# quadstep.net
KiCad netlist of a schematic drawn in EAGLE
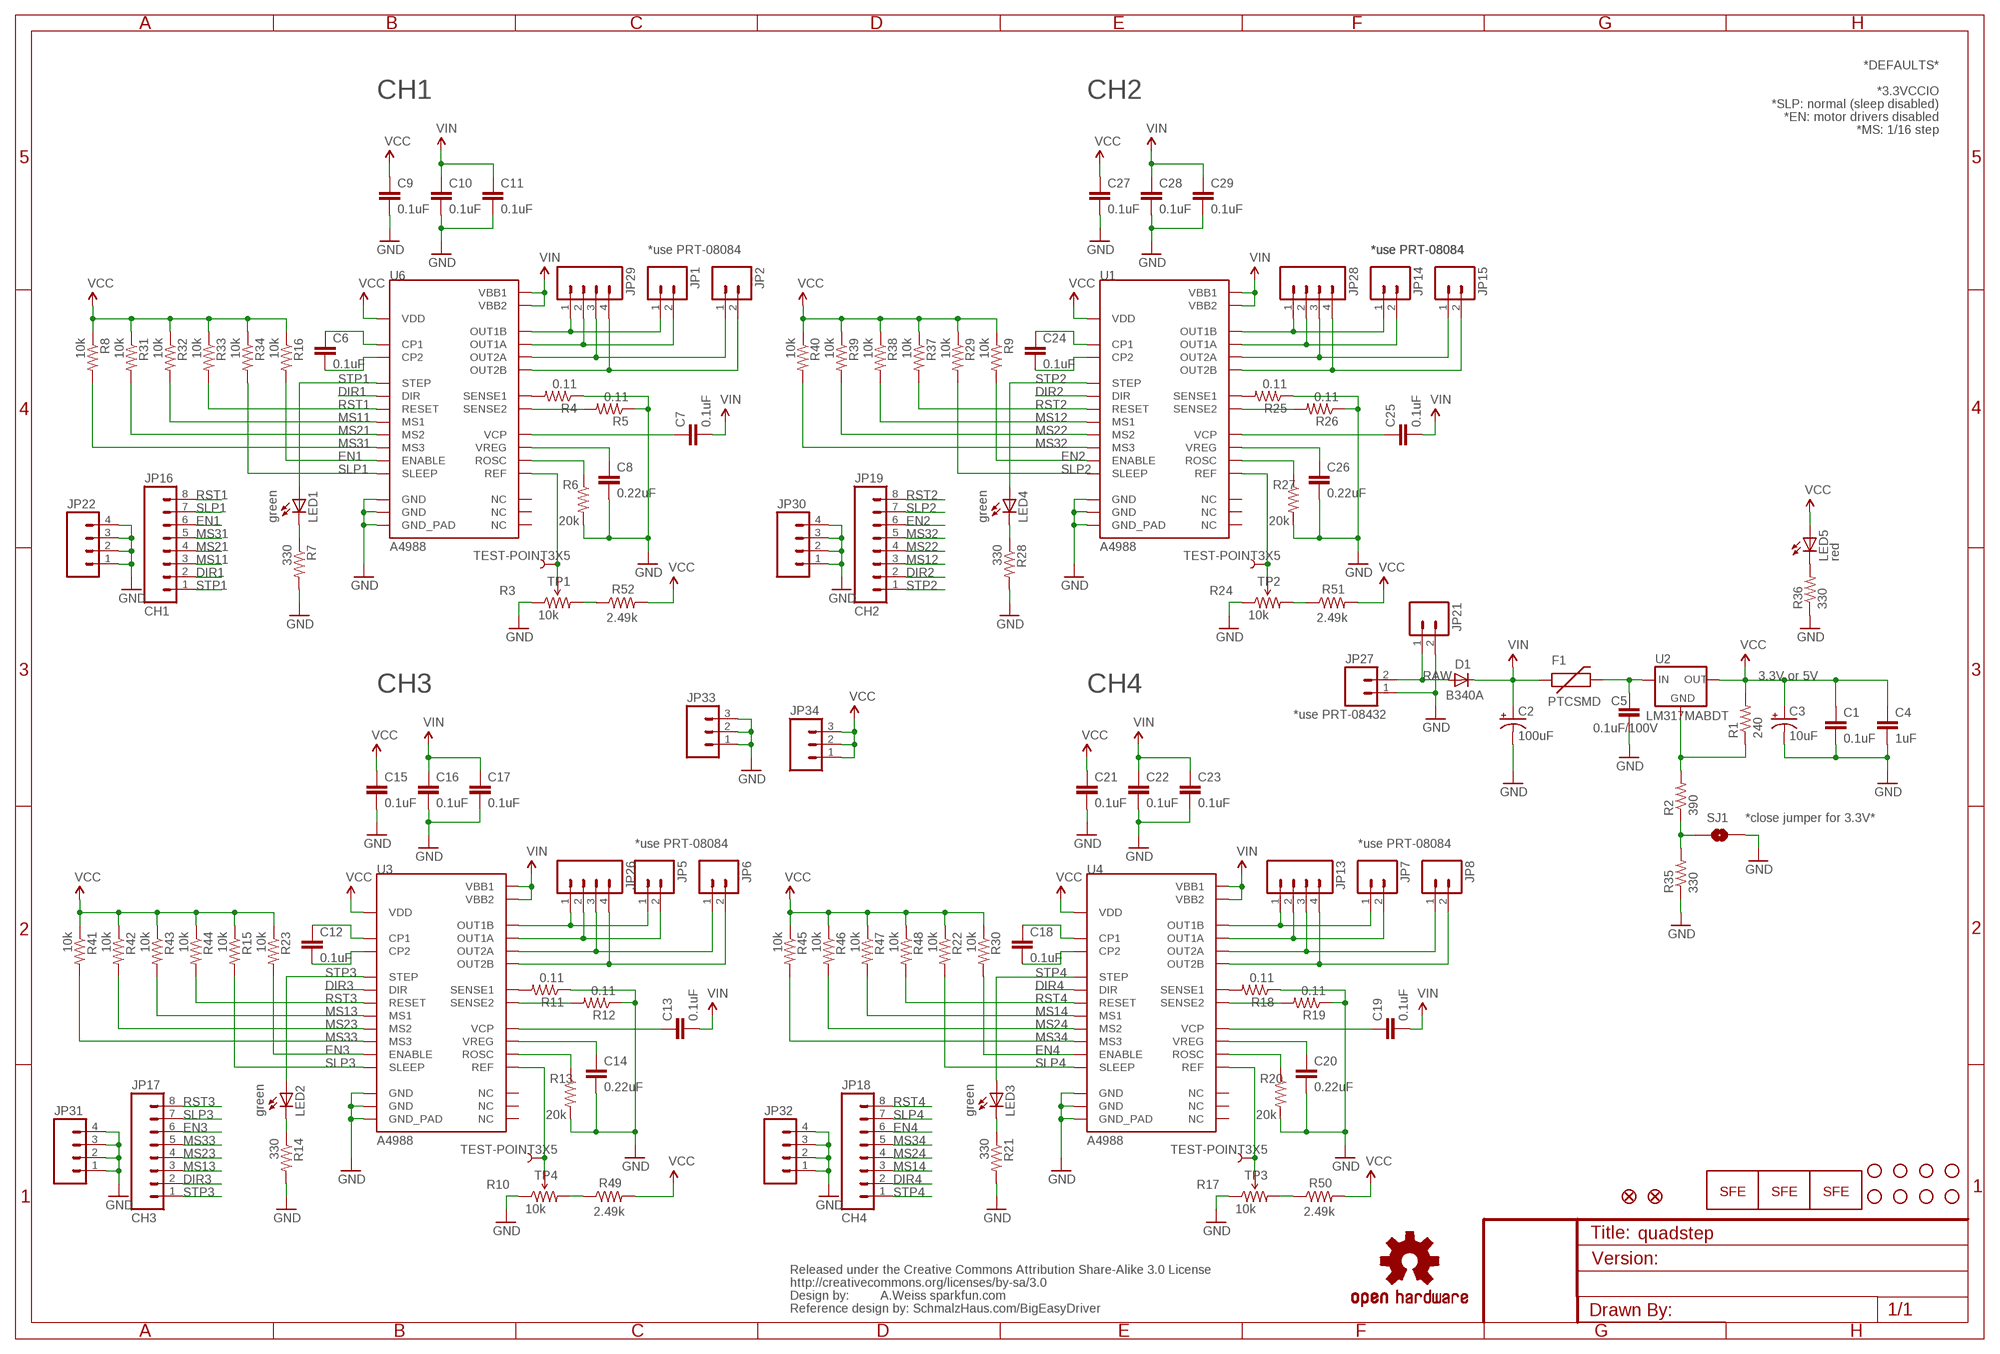
[diagram p0: schematic, sheet 1]

(export (version "E")
  (design (tool "Eeschema 10.0.6"))
  (components
    (comp (ref "C1")
      (value "0.1uF")
      (footprint "eagle-import:0402-CAP")
      (libsource (lib "eagle-import") (part "CAP0402-CAP"))
    )
    (comp (ref "C2")
      (value "100uF")
      (footprint "eagle-import:PANASONIC_G")
      (libsource (lib "eagle-import") (part "CAP_POLG"))
    )
    (comp (ref "C3")
      (value "10uF")
      (footprint "eagle-import:EIA3216")
      (libsource (lib "eagle-import") (part "CAP_POL1206"))
    )
    (comp (ref "C4")
      (value "1uF")
      (footprint "eagle-import:0805")
      (libsource (lib "eagle-import") (part "CAP0805"))
    )
    (comp (ref "C5")
      (value "0.1uF/100V")
      (footprint "eagle-import:0402-CAP")
      (libsource (lib "eagle-import") (part "CAP0402-CAP"))
    )
    (comp (ref "C6")
      (value "0.1uF")
      (footprint "eagle-import:0402-CAP")
      (libsource (lib "eagle-import") (part "CAP0402-CAP"))
    )
    (comp (ref "C7")
      (value "0.1uF")
      (footprint "eagle-import:0402-CAP")
      (libsource (lib "eagle-import") (part "CAP0402-CAP"))
    )
    (comp (ref "C8")
      (value "0.22uF")
      (footprint "eagle-import:0402-CAP")
      (libsource (lib "eagle-import") (part "CAP0402-CAP"))
    )
    (comp (ref "C9")
      (value "0.1uF")
      (footprint "eagle-import:0402-CAP")
      (libsource (lib "eagle-import") (part "CAP0402-CAP"))
    )
    (comp (ref "C10")
      (value "0.1uF")
      (footprint "eagle-import:0402-CAP")
      (libsource (lib "eagle-import") (part "CAP0402-CAP"))
    )
    (comp (ref "C11")
      (value "0.1uF")
      (footprint "eagle-import:0402-CAP")
      (libsource (lib "eagle-import") (part "CAP0402-CAP"))
    )
    (comp (ref "C12")
      (value "0.1uF")
      (footprint "eagle-import:0402-CAP")
      (libsource (lib "eagle-import") (part "CAP0402-CAP"))
    )
    (comp (ref "C13")
      (value "0.1uF")
      (footprint "eagle-import:0402-CAP")
      (libsource (lib "eagle-import") (part "CAP0402-CAP"))
    )
    (comp (ref "C14")
      (value "0.22uF")
      (footprint "eagle-import:0402-CAP")
      (libsource (lib "eagle-import") (part "CAP0402-CAP"))
    )
    (comp (ref "C15")
      (value "0.1uF")
      (footprint "eagle-import:0402-CAP")
      (libsource (lib "eagle-import") (part "CAP0402-CAP"))
    )
    (comp (ref "C16")
      (value "0.1uF")
      (footprint "eagle-import:0402-CAP")
      (libsource (lib "eagle-import") (part "CAP0402-CAP"))
    )
    (comp (ref "C17")
      (value "0.1uF")
      (footprint "eagle-import:0402-CAP")
      (libsource (lib "eagle-import") (part "CAP0402-CAP"))
    )
    (comp (ref "C18")
      (value "0.1uF")
      (footprint "eagle-import:0402-CAP")
      (libsource (lib "eagle-import") (part "CAP0402-CAP"))
    )
    (comp (ref "C19")
      (value "0.1uF")
      (footprint "eagle-import:0402-CAP")
      (libsource (lib "eagle-import") (part "CAP0402-CAP"))
    )
    (comp (ref "C20")
      (value "0.22uF")
      (footprint "eagle-import:0402-CAP")
      (libsource (lib "eagle-import") (part "CAP0402-CAP"))
    )
    (comp (ref "C21")
      (value "0.1uF")
      (footprint "eagle-import:0402-CAP")
      (libsource (lib "eagle-import") (part "CAP0402-CAP"))
    )
    (comp (ref "C22")
      (value "0.1uF")
      (footprint "eagle-import:0402-CAP")
      (libsource (lib "eagle-import") (part "CAP0402-CAP"))
    )
    (comp (ref "C23")
      (value "0.1uF")
      (footprint "eagle-import:0402-CAP")
      (libsource (lib "eagle-import") (part "CAP0402-CAP"))
    )
    (comp (ref "C24")
      (value "0.1uF")
      (footprint "eagle-import:0402-CAP")
      (libsource (lib "eagle-import") (part "CAP0402-CAP"))
    )
    (comp (ref "C25")
      (value "0.1uF")
      (footprint "eagle-import:0402-CAP")
      (libsource (lib "eagle-import") (part "CAP0402-CAP"))
    )
    (comp (ref "C26")
      (value "0.22uF")
      (footprint "eagle-import:0402-CAP")
      (libsource (lib "eagle-import") (part "CAP0402-CAP"))
    )
    (comp (ref "C27")
      (value "0.1uF")
      (footprint "eagle-import:0402-CAP")
      (libsource (lib "eagle-import") (part "CAP0402-CAP"))
    )
    (comp (ref "C28")
      (value "0.1uF")
      (footprint "eagle-import:0402-CAP")
      (libsource (lib "eagle-import") (part "CAP0402-CAP"))
    )
    (comp (ref "C29")
      (value "0.1uF")
      (footprint "eagle-import:0402-CAP")
      (libsource (lib "eagle-import") (part "CAP0402-CAP"))
    )
    (comp (ref "CC_TEXT1")
      (value "CREATIVE_COMMONS")
      (footprint "eagle-import:CREATIVE_COMMONS")
      (libsource (lib "eagle-import") (part "CREATIVE_COMMONS"))
    )
    (comp (ref "D1")
      (value "B340A")
      (footprint "eagle-import:SMA-DIODE")
      (libsource (lib "eagle-import") (part "DIODESMA"))
    )
    (comp (ref "F1")
      (value "PTCSMD")
      (footprint "eagle-import:PTC-1206")
      (libsource (lib "eagle-import") (part "PTCSMD"))
    )
    (comp (ref "JP1")
      (value "M023.5MM_LOCK")
      (footprint "eagle-import:SCREWTERMINAL-3.5MM-2_LOCK")
      (libsource (lib "eagle-import") (part "M023.5MM_LOCK"))
    )
    (comp (ref "JP2")
      (value "M023.5MM_LOCK")
      (footprint "eagle-import:SCREWTERMINAL-3.5MM-2_LOCK")
      (libsource (lib "eagle-import") (part "M023.5MM_LOCK"))
    )
    (comp (ref "JP5")
      (value "M023.5MM_LOCK")
      (footprint "eagle-import:SCREWTERMINAL-3.5MM-2_LOCK")
      (libsource (lib "eagle-import") (part "M023.5MM_LOCK"))
    )
    (comp (ref "JP6")
      (value "M023.5MM_LOCK")
      (footprint "eagle-import:SCREWTERMINAL-3.5MM-2_LOCK")
      (libsource (lib "eagle-import") (part "M023.5MM_LOCK"))
    )
    (comp (ref "JP7")
      (value "M023.5MM_LOCK")
      (footprint "eagle-import:SCREWTERMINAL-3.5MM-2_LOCK")
      (libsource (lib "eagle-import") (part "M023.5MM_LOCK"))
    )
    (comp (ref "JP8")
      (value "M023.5MM_LOCK")
      (footprint "eagle-import:SCREWTERMINAL-3.5MM-2_LOCK")
      (libsource (lib "eagle-import") (part "M023.5MM_LOCK"))
    )
    (comp (ref "JP9")
      (value "STAND-OFF")
      (footprint "eagle-import:STAND-OFF")
      (libsource (lib "eagle-import") (part "STAND-OFF"))
    )
    (comp (ref "JP10")
      (value "STAND-OFF")
      (footprint "eagle-import:STAND-OFF")
      (libsource (lib "eagle-import") (part "STAND-OFF"))
    )
    (comp (ref "JP11")
      (value "STAND-OFF")
      (footprint "eagle-import:STAND-OFF")
      (libsource (lib "eagle-import") (part "STAND-OFF"))
    )
    (comp (ref "JP12")
      (value "STAND-OFF")
      (footprint "eagle-import:STAND-OFF")
      (libsource (lib "eagle-import") (part "STAND-OFF"))
    )
    (comp (ref "JP13")
      (value "M04PTH")
      (footprint "eagle-import:1X04")
      (libsource (lib "eagle-import") (part "M04PTH"))
    )
    (comp (ref "JP14")
      (value "M023.5MM_LOCK")
      (footprint "eagle-import:SCREWTERMINAL-3.5MM-2_LOCK")
      (libsource (lib "eagle-import") (part "M023.5MM_LOCK"))
    )
    (comp (ref "JP15")
      (value "M023.5MM_LOCK")
      (footprint "eagle-import:SCREWTERMINAL-3.5MM-2_LOCK")
      (libsource (lib "eagle-import") (part "M023.5MM_LOCK"))
    )
    (comp (ref "JP16")
      (value "CH1")
      (footprint "eagle-import:1X08")
      (libsource (lib "eagle-import") (part "M08"))
    )
    (comp (ref "JP17")
      (value "CH3")
      (footprint "eagle-import:1X08")
      (libsource (lib "eagle-import") (part "M08"))
    )
    (comp (ref "JP18")
      (value "CH4")
      (footprint "eagle-import:1X08")
      (libsource (lib "eagle-import") (part "M08"))
    )
    (comp (ref "JP19")
      (value "CH2")
      (footprint "eagle-import:1X08")
      (libsource (lib "eagle-import") (part "M08"))
    )
    (comp (ref "JP20")
      (value "LOGO-SFENEW")
      (footprint "eagle-import:SFE-NEW-WEBLOGO")
      (libsource (lib "eagle-import") (part "LOGO-SFENEW"))
    )
    (comp (ref "JP21")
      (value "M025MM")
      (footprint "eagle-import:SCREWTERMINAL-5MM-2")
      (libsource (lib "eagle-import") (part "M025MM"))
    )
    (comp (ref "JP22")
      (value "M04PTH")
      (footprint "eagle-import:1X04")
      (libsource (lib "eagle-import") (part "M04PTH"))
    )
    (comp (ref "JP23")
      (value "LOGO-SFESK")
      (footprint "eagle-import:SFE-LOGO-FLAME")
      (libsource (lib "eagle-import") (part "LOGO-SFESK"))
    )
    (comp (ref "JP24")
      (value "FIDUCIAL1X2")
      (footprint "eagle-import:FIDUCIAL-1X2")
      (libsource (lib "eagle-import") (part "FIDUCIAL1X2"))
    )
    (comp (ref "JP25")
      (value "FIDUCIAL1X2")
      (footprint "eagle-import:FIDUCIAL-1X2")
      (libsource (lib "eagle-import") (part "FIDUCIAL1X2"))
    )
    (comp (ref "JP26")
      (value "M04PTH")
      (footprint "eagle-import:1X04")
      (libsource (lib "eagle-import") (part "M04PTH"))
    )
    (comp (ref "JP27")
      (value "M02PTH")
      (footprint "eagle-import:1X02")
      (libsource (lib "eagle-import") (part "SparkFun-Connectors_M02PTH"))
    )
    (comp (ref "JP28")
      (value "M04PTH")
      (footprint "eagle-import:1X04")
      (libsource (lib "eagle-import") (part "M04PTH"))
    )
    (comp (ref "JP29")
      (value "M04PTH")
      (footprint "eagle-import:1X04")
      (libsource (lib "eagle-import") (part "M04PTH"))
    )
    (comp (ref "JP30")
      (value "M04PTH")
      (footprint "eagle-import:1X04")
      (libsource (lib "eagle-import") (part "M04PTH"))
    )
    (comp (ref "JP31")
      (value "M04PTH")
      (footprint "eagle-import:1X04")
      (libsource (lib "eagle-import") (part "M04PTH"))
    )
    (comp (ref "JP32")
      (value "M04PTH")
      (footprint "eagle-import:1X04")
      (libsource (lib "eagle-import") (part "M04PTH"))
    )
    (comp (ref "JP33")
      (value "M03PTH")
      (footprint "eagle-import:1X03")
      (libsource (lib "eagle-import") (part "M03PTH"))
    )
    (comp (ref "JP34")
      (value "M03PTH")
      (footprint "eagle-import:1X03")
      (libsource (lib "eagle-import") (part "M03PTH"))
    )
    (comp (ref "LED1")
      (value "green")
      (footprint "eagle-import:LED-0603")
      (libsource (lib "eagle-import") (part "LED0603"))
    )
    (comp (ref "LED2")
      (value "green")
      (footprint "eagle-import:LED-0603")
      (libsource (lib "eagle-import") (part "LED0603"))
    )
    (comp (ref "LED3")
      (value "green")
      (footprint "eagle-import:LED-0603")
      (libsource (lib "eagle-import") (part "LED0603"))
    )
    (comp (ref "LED4")
      (value "green")
      (footprint "eagle-import:LED-0603")
      (libsource (lib "eagle-import") (part "LED0603"))
    )
    (comp (ref "LED5")
      (value "red")
      (footprint "eagle-import:LED-0603")
      (libsource (lib "eagle-import") (part "LED0603"))
    )
    (comp (ref "LOGO1")
      (value "LOGO-SFENW2")
      (footprint "eagle-import:SFE-NEW-WEB")
      (libsource (lib "eagle-import") (part "SparkFun-Aesthetics_LOGO-SFENW2"))
    )
    (comp (ref "R1")
      (value "240")
      (footprint "eagle-import:0402-RES")
      (libsource (lib "eagle-import") (part "RESISTOR0402-RES"))
    )
    (comp (ref "R2")
      (value "390")
      (footprint "eagle-import:0402-RES")
      (libsource (lib "eagle-import") (part "RESISTOR0402-RES"))
    )
    (comp (ref "R3")
      (value "10k")
      (footprint "eagle-import:TRIMPOT-3MM")
      (libsource (lib "eagle-import") (part "TRIMPOTSMD"))
    )
    (comp (ref "R4")
      (value "0.11")
      (footprint "eagle-import:R2010")
      (libsource (lib "eagle-import") (part "RESISTOR2010"))
    )
    (comp (ref "R5")
      (value "0.11")
      (footprint "eagle-import:R2010")
      (libsource (lib "eagle-import") (part "RESISTOR2010"))
    )
    (comp (ref "R6")
      (value "20k")
      (footprint "eagle-import:0402-RES")
      (libsource (lib "eagle-import") (part "RESISTOR0402-RES"))
    )
    (comp (ref "R7")
      (value "330")
      (footprint "eagle-import:0402-RES")
      (libsource (lib "eagle-import") (part "RESISTOR0402-RES"))
    )
    (comp (ref "R8")
      (value "10k")
      (footprint "eagle-import:0402-RES")
      (libsource (lib "eagle-import") (part "RESISTOR0402-RES"))
    )
    (comp (ref "R9")
      (value "10k")
      (footprint "eagle-import:0402-RES")
      (libsource (lib "eagle-import") (part "RESISTOR0402-RES"))
    )
    (comp (ref "R10")
      (value "10k")
      (footprint "eagle-import:TRIMPOT-3MM")
      (libsource (lib "eagle-import") (part "TRIMPOTSMD"))
    )
    (comp (ref "R11")
      (value "0.11")
      (footprint "eagle-import:R2010")
      (libsource (lib "eagle-import") (part "RESISTOR2010"))
    )
    (comp (ref "R12")
      (value "0.11")
      (footprint "eagle-import:R2010")
      (libsource (lib "eagle-import") (part "RESISTOR2010"))
    )
    (comp (ref "R13")
      (value "20k")
      (footprint "eagle-import:0402-RES")
      (libsource (lib "eagle-import") (part "RESISTOR0402-RES"))
    )
    (comp (ref "R14")
      (value "330")
      (footprint "eagle-import:0402-RES")
      (libsource (lib "eagle-import") (part "RESISTOR0402-RES"))
    )
    (comp (ref "R15")
      (value "10k")
      (footprint "eagle-import:0402-RES")
      (libsource (lib "eagle-import") (part "RESISTOR0402-RES"))
    )
    (comp (ref "R16")
      (value "10k")
      (footprint "eagle-import:0402-RES")
      (libsource (lib "eagle-import") (part "RESISTOR0402-RES"))
    )
    (comp (ref "R17")
      (value "10k")
      (footprint "eagle-import:TRIMPOT-3MM")
      (libsource (lib "eagle-import") (part "TRIMPOTSMD"))
    )
    (comp (ref "R18")
      (value "0.11")
      (footprint "eagle-import:R2010")
      (libsource (lib "eagle-import") (part "RESISTOR2010"))
    )
    (comp (ref "R19")
      (value "0.11")
      (footprint "eagle-import:R2010")
      (libsource (lib "eagle-import") (part "RESISTOR2010"))
    )
    (comp (ref "R20")
      (value "20k")
      (footprint "eagle-import:0402-RES")
      (libsource (lib "eagle-import") (part "RESISTOR0402-RES"))
    )
    (comp (ref "R21")
      (value "330")
      (footprint "eagle-import:0402-RES")
      (libsource (lib "eagle-import") (part "RESISTOR0402-RES"))
    )
    (comp (ref "R22")
      (value "10k")
      (footprint "eagle-import:0402-RES")
      (libsource (lib "eagle-import") (part "RESISTOR0402-RES"))
    )
    (comp (ref "R23")
      (value "10k")
      (footprint "eagle-import:0402-RES")
      (libsource (lib "eagle-import") (part "RESISTOR0402-RES"))
    )
    (comp (ref "R24")
      (value "10k")
      (footprint "eagle-import:TRIMPOT-3MM")
      (libsource (lib "eagle-import") (part "TRIMPOTSMD"))
    )
    (comp (ref "R25")
      (value "0.11")
      (footprint "eagle-import:R2010")
      (libsource (lib "eagle-import") (part "RESISTOR2010"))
    )
    (comp (ref "R26")
      (value "0.11")
      (footprint "eagle-import:R2010")
      (libsource (lib "eagle-import") (part "RESISTOR2010"))
    )
    (comp (ref "R27")
      (value "20k")
      (footprint "eagle-import:0402-RES")
      (libsource (lib "eagle-import") (part "RESISTOR0402-RES"))
    )
    (comp (ref "R28")
      (value "330")
      (footprint "eagle-import:0402-RES")
      (libsource (lib "eagle-import") (part "RESISTOR0402-RES"))
    )
    (comp (ref "R29")
      (value "10k")
      (footprint "eagle-import:0402-RES")
      (libsource (lib "eagle-import") (part "RESISTOR0402-RES"))
    )
    (comp (ref "R30")
      (value "10k")
      (footprint "eagle-import:0402-RES")
      (libsource (lib "eagle-import") (part "RESISTOR0402-RES"))
    )
    (comp (ref "R31")
      (value "10k")
      (footprint "eagle-import:0402-RES")
      (libsource (lib "eagle-import") (part "RESISTOR0402-RES"))
    )
    (comp (ref "R32")
      (value "10k")
      (footprint "eagle-import:0402-RES")
      (libsource (lib "eagle-import") (part "RESISTOR0402-RES"))
    )
    (comp (ref "R33")
      (value "10k")
      (footprint "eagle-import:0402-RES")
      (libsource (lib "eagle-import") (part "RESISTOR0402-RES"))
    )
    (comp (ref "R34")
      (value "10k")
      (footprint "eagle-import:0402-RES")
      (libsource (lib "eagle-import") (part "RESISTOR0402-RES"))
    )
    (comp (ref "R35")
      (value "330")
      (footprint "eagle-import:0402-RES")
      (libsource (lib "eagle-import") (part "RESISTOR0402-RES"))
    )
    (comp (ref "R36")
      (value "330")
      (footprint "eagle-import:0402-RES")
      (libsource (lib "eagle-import") (part "RESISTOR0402-RES"))
    )
    (comp (ref "R37")
      (value "10k")
      (footprint "eagle-import:0402-RES")
      (libsource (lib "eagle-import") (part "RESISTOR0402-RES"))
    )
    (comp (ref "R38")
      (value "10k")
      (footprint "eagle-import:0402-RES")
      (libsource (lib "eagle-import") (part "RESISTOR0402-RES"))
    )
    (comp (ref "R39")
      (value "10k")
      (footprint "eagle-import:0402-RES")
      (libsource (lib "eagle-import") (part "RESISTOR0402-RES"))
    )
    (comp (ref "R40")
      (value "10k")
      (footprint "eagle-import:0402-RES")
      (libsource (lib "eagle-import") (part "RESISTOR0402-RES"))
    )
    (comp (ref "R41")
      (value "10k")
      (footprint "eagle-import:0402-RES")
      (libsource (lib "eagle-import") (part "RESISTOR0402-RES"))
    )
    (comp (ref "R42")
      (value "10k")
      (footprint "eagle-import:0402-RES")
      (libsource (lib "eagle-import") (part "RESISTOR0402-RES"))
    )
    (comp (ref "R43")
      (value "10k")
      (footprint "eagle-import:0402-RES")
      (libsource (lib "eagle-import") (part "RESISTOR0402-RES"))
    )
    (comp (ref "R44")
      (value "10k")
      (footprint "eagle-import:0402-RES")
      (libsource (lib "eagle-import") (part "RESISTOR0402-RES"))
    )
    (comp (ref "R45")
      (value "10k")
      (footprint "eagle-import:0402-RES")
      (libsource (lib "eagle-import") (part "RESISTOR0402-RES"))
    )
    (comp (ref "R46")
      (value "10k")
      (footprint "eagle-import:0402-RES")
      (libsource (lib "eagle-import") (part "RESISTOR0402-RES"))
    )
    (comp (ref "R47")
      (value "10k")
      (footprint "eagle-import:0402-RES")
      (libsource (lib "eagle-import") (part "RESISTOR0402-RES"))
    )
    (comp (ref "R48")
      (value "10k")
      (footprint "eagle-import:0402-RES")
      (libsource (lib "eagle-import") (part "RESISTOR0402-RES"))
    )
    (comp (ref "R49")
      (value "2.49k")
      (footprint "eagle-import:0402-RES")
      (libsource (lib "eagle-import") (part "RESISTOR0402-RES"))
    )
    (comp (ref "R50")
      (value "2.49k")
      (footprint "eagle-import:0402-RES")
      (libsource (lib "eagle-import") (part "RESISTOR0402-RES"))
    )
    (comp (ref "R51")
      (value "2.49k")
      (footprint "eagle-import:0402-RES")
      (libsource (lib "eagle-import") (part "RESISTOR0402-RES"))
    )
    (comp (ref "R52")
      (value "2.49k")
      (footprint "eagle-import:0402-RES")
      (libsource (lib "eagle-import") (part "RESISTOR0402-RES"))
    )
    (comp (ref "SJ1")
      (value "SOLDERJUMPERNO")
      (footprint "eagle-import:SJ_2S-NO")
      (libsource (lib "eagle-import") (part "SOLDERJUMPERNO"))
    )
    (comp (ref "STANDOFF1")
      (value "STAND-OFFTIGHT")
      (footprint "eagle-import:STAND-OFF-TIGHT")
      (libsource (lib "eagle-import") (part "SparkFun-Electromechanical_STAND-OFFTIGHT"))
    )
    (comp (ref "STANDOFF2")
      (value "STAND-OFFTIGHT")
      (footprint "eagle-import:STAND-OFF-TIGHT")
      (libsource (lib "eagle-import") (part "SparkFun-Electromechanical_STAND-OFFTIGHT"))
    )
    (comp (ref "STANDOFF3")
      (value "STAND-OFFTIGHT")
      (footprint "eagle-import:STAND-OFF-TIGHT")
      (libsource (lib "eagle-import") (part "SparkFun-Electromechanical_STAND-OFFTIGHT"))
    )
    (comp (ref "STANDOFF4")
      (value "STAND-OFFTIGHT")
      (footprint "eagle-import:STAND-OFF-TIGHT")
      (libsource (lib "eagle-import") (part "SparkFun-Electromechanical_STAND-OFFTIGHT"))
    )
    (comp (ref "TP1")
      (value "TEST-POINT3X5")
      (footprint "eagle-import:PAD.03X.05")
      (libsource (lib "eagle-import") (part "TEST-POINT3X5"))
    )
    (comp (ref "TP2")
      (value "TEST-POINT3X5")
      (footprint "eagle-import:PAD.03X.05")
      (libsource (lib "eagle-import") (part "TEST-POINT3X5"))
    )
    (comp (ref "TP3")
      (value "TEST-POINT3X5")
      (footprint "eagle-import:PAD.03X.05")
      (libsource (lib "eagle-import") (part "TEST-POINT3X5"))
    )
    (comp (ref "TP4")
      (value "TEST-POINT3X5")
      (footprint "eagle-import:PAD.03X.05")
      (libsource (lib "eagle-import") (part "TEST-POINT3X5"))
    )
    (comp (ref "U$1")
      (value "OSHW-LOGOS")
      (footprint "eagle-import:OSHW-LOGO-S")
      (libsource (lib "eagle-import") (part "OSHW-LOGOS"))
    )
    (comp (ref "U1")
      (value "A4988")
      (footprint "eagle-import:QFN-28-5MM-1_1")
      (libsource (lib "eagle-import") (part "A49831{colon}1"))
    )
    (comp (ref "U2")
      (value "LM317MABDT")
      (footprint "eagle-import:DPAK")
      (libsource (lib "eagle-import") (part "V_REG_MC33269DT"))
    )
    (comp (ref "U3")
      (value "A4988")
      (footprint "eagle-import:QFN-28-5MM-1_1")
      (libsource (lib "eagle-import") (part "A49831{colon}1"))
    )
    (comp (ref "U4")
      (value "A4988")
      (footprint "eagle-import:QFN-28-5MM-1_1")
      (libsource (lib "eagle-import") (part "A49831{colon}1"))
    )
    (comp (ref "U6")
      (value "A4988")
      (footprint "eagle-import:QFN-28-5MM-1_1")
      (libsource (lib "eagle-import") (part "A49831{colon}1"))
    )
  )
  (nets
    (net (code "1") (name "/DIR1") (class "Default")
      (node (ref "JP16") (pin "2") (pinfunction "2_2") (pintype "passive"))
      (node (ref "U6") (pin "P$19") (pinfunction "DIR_P$19") (pintype "input"))
    )
    (net (code "2") (name "/DIR2") (class "Default")
      (node (ref "JP19") (pin "2") (pinfunction "2_2") (pintype "passive"))
      (node (ref "U1") (pin "P$19") (pinfunction "DIR_P$19") (pintype "input"))
    )
    (net (code "3") (name "/DIR3") (class "Default")
      (node (ref "JP17") (pin "2") (pinfunction "2_2") (pintype "passive"))
      (node (ref "U3") (pin "P$19") (pinfunction "DIR_P$19") (pintype "input"))
    )
    (net (code "4") (name "/DIR4") (class "Default")
      (node (ref "JP18") (pin "2") (pinfunction "2_2") (pintype "passive"))
      (node (ref "U4") (pin "P$19") (pinfunction "DIR_P$19") (pintype "input"))
    )
    (net (code "5") (name "/EN1") (class "Default")
      (node (ref "JP16") (pin "6") (pinfunction "6_6") (pintype "passive"))
      (node (ref "R16") (pin "2") (pinfunction "2_2") (pintype "passive"))
      (node (ref "U6") (pin "P$2") (pinfunction "ENABLE_P$2") (pintype "input"))
    )
    (net (code "6") (name "/EN2") (class "Default")
      (node (ref "JP19") (pin "6") (pinfunction "6_6") (pintype "passive"))
      (node (ref "R9") (pin "2") (pinfunction "2_2") (pintype "passive"))
      (node (ref "U1") (pin "P$2") (pinfunction "ENABLE_P$2") (pintype "input"))
    )
    (net (code "7") (name "/EN3") (class "Default")
      (node (ref "JP17") (pin "6") (pinfunction "6_6") (pintype "passive"))
      (node (ref "R23") (pin "2") (pinfunction "2_2") (pintype "passive"))
      (node (ref "U3") (pin "P$2") (pinfunction "ENABLE_P$2") (pintype "input"))
    )
    (net (code "8") (name "/EN4") (class "Default")
      (node (ref "JP18") (pin "6") (pinfunction "6_6") (pintype "passive"))
      (node (ref "R30") (pin "2") (pinfunction "2_2") (pintype "passive"))
      (node (ref "U4") (pin "P$2") (pinfunction "ENABLE_P$2") (pintype "input"))
    )
    (net (code "9") (name "/MS11") (class "Default")
      (node (ref "JP16") (pin "3") (pinfunction "3_3") (pintype "passive"))
      (node (ref "R32") (pin "2") (pinfunction "2_2") (pintype "passive"))
      (node (ref "U6") (pin "P$9") (pinfunction "MS1_P$9") (pintype "input"))
    )
    (net (code "10") (name "/MS12") (class "Default")
      (node (ref "JP19") (pin "3") (pinfunction "3_3") (pintype "passive"))
      (node (ref "R38") (pin "2") (pinfunction "2_2") (pintype "passive"))
      (node (ref "U1") (pin "P$9") (pinfunction "MS1_P$9") (pintype "input"))
    )
    (net (code "11") (name "/MS13") (class "Default")
      (node (ref "JP17") (pin "3") (pinfunction "3_3") (pintype "passive"))
      (node (ref "R43") (pin "2") (pinfunction "2_2") (pintype "passive"))
      (node (ref "U3") (pin "P$9") (pinfunction "MS1_P$9") (pintype "input"))
    )
    (net (code "12") (name "/MS14") (class "Default")
      (node (ref "JP18") (pin "3") (pinfunction "3_3") (pintype "passive"))
      (node (ref "R47") (pin "2") (pinfunction "2_2") (pintype "passive"))
      (node (ref "U4") (pin "P$9") (pinfunction "MS1_P$9") (pintype "input"))
    )
    (net (code "13") (name "/MS21") (class "Default")
      (node (ref "JP16") (pin "4") (pinfunction "4_4") (pintype "passive"))
      (node (ref "R31") (pin "2") (pinfunction "2_2") (pintype "passive"))
      (node (ref "U6") (pin "P$10") (pinfunction "MS2_P$10") (pintype "input"))
    )
    (net (code "14") (name "/MS22") (class "Default")
      (node (ref "JP19") (pin "4") (pinfunction "4_4") (pintype "passive"))
      (node (ref "R39") (pin "2") (pinfunction "2_2") (pintype "passive"))
      (node (ref "U1") (pin "P$10") (pinfunction "MS2_P$10") (pintype "input"))
    )
    (net (code "15") (name "/MS23") (class "Default")
      (node (ref "JP17") (pin "4") (pinfunction "4_4") (pintype "passive"))
      (node (ref "R42") (pin "2") (pinfunction "2_2") (pintype "passive"))
      (node (ref "U3") (pin "P$10") (pinfunction "MS2_P$10") (pintype "input"))
    )
    (net (code "16") (name "/MS24") (class "Default")
      (node (ref "JP18") (pin "4") (pinfunction "4_4") (pintype "passive"))
      (node (ref "R46") (pin "2") (pinfunction "2_2") (pintype "passive"))
      (node (ref "U4") (pin "P$10") (pinfunction "MS2_P$10") (pintype "input"))
    )
    (net (code "17") (name "/MS31") (class "Default")
      (node (ref "JP16") (pin "5") (pinfunction "5_5") (pintype "passive"))
      (node (ref "R8") (pin "2") (pinfunction "2_2") (pintype "passive"))
      (node (ref "U6") (pin "P$11") (pinfunction "MS3_P$11") (pintype "input"))
    )
    (net (code "18") (name "/MS32") (class "Default")
      (node (ref "JP19") (pin "5") (pinfunction "5_5") (pintype "passive"))
      (node (ref "R40") (pin "2") (pinfunction "2_2") (pintype "passive"))
      (node (ref "U1") (pin "P$11") (pinfunction "MS3_P$11") (pintype "input"))
    )
    (net (code "19") (name "/MS33") (class "Default")
      (node (ref "JP17") (pin "5") (pinfunction "5_5") (pintype "passive"))
      (node (ref "R41") (pin "2") (pinfunction "2_2") (pintype "passive"))
      (node (ref "U3") (pin "P$11") (pinfunction "MS3_P$11") (pintype "input"))
    )
    (net (code "20") (name "/MS34") (class "Default")
      (node (ref "JP18") (pin "5") (pinfunction "5_5") (pintype "passive"))
      (node (ref "R45") (pin "2") (pinfunction "2_2") (pintype "passive"))
      (node (ref "U4") (pin "P$11") (pinfunction "MS3_P$11") (pintype "input"))
    )
    (net (code "21") (name "/RAW") (class "Default")
      (node (ref "D1") (pin "A") (pinfunction "A_A") (pintype "passive"))
      (node (ref "JP21") (pin "1") (pinfunction "1_1") (pintype "passive"))
      (node (ref "JP27") (pin "2") (pinfunction "2_2") (pintype "passive"))
    )
    (net (code "22") (name "/RST1") (class "Default")
      (node (ref "JP16") (pin "8") (pinfunction "8_8") (pintype "passive"))
      (node (ref "R33") (pin "2") (pinfunction "2_2") (pintype "passive"))
      (node (ref "U6") (pin "P$12") (pinfunction "RESET_P$12") (pintype "input"))
    )
    (net (code "23") (name "/RST2") (class "Default")
      (node (ref "JP19") (pin "8") (pinfunction "8_8") (pintype "passive"))
      (node (ref "R37") (pin "2") (pinfunction "2_2") (pintype "passive"))
      (node (ref "U1") (pin "P$12") (pinfunction "RESET_P$12") (pintype "input"))
    )
    (net (code "24") (name "/RST3") (class "Default")
      (node (ref "JP17") (pin "8") (pinfunction "8_8") (pintype "passive"))
      (node (ref "R44") (pin "2") (pinfunction "2_2") (pintype "passive"))
      (node (ref "U3") (pin "P$12") (pinfunction "RESET_P$12") (pintype "input"))
    )
    (net (code "25") (name "/RST4") (class "Default")
      (node (ref "JP18") (pin "8") (pinfunction "8_8") (pintype "passive"))
      (node (ref "R48") (pin "2") (pinfunction "2_2") (pintype "passive"))
      (node (ref "U4") (pin "P$12") (pinfunction "RESET_P$12") (pintype "input"))
    )
    (net (code "26") (name "/SLP1") (class "Default")
      (node (ref "JP16") (pin "7") (pinfunction "7_7") (pintype "passive"))
      (node (ref "R34") (pin "2") (pinfunction "2_2") (pintype "passive"))
      (node (ref "U6") (pin "P$14") (pinfunction "SLEEP_P$14") (pintype "input"))
    )
    (net (code "27") (name "/SLP2") (class "Default")
      (node (ref "JP19") (pin "7") (pinfunction "7_7") (pintype "passive"))
      (node (ref "R29") (pin "2") (pinfunction "2_2") (pintype "passive"))
      (node (ref "U1") (pin "P$14") (pinfunction "SLEEP_P$14") (pintype "input"))
    )
    (net (code "28") (name "/SLP3") (class "Default")
      (node (ref "JP17") (pin "7") (pinfunction "7_7") (pintype "passive"))
      (node (ref "R15") (pin "2") (pinfunction "2_2") (pintype "passive"))
      (node (ref "U3") (pin "P$14") (pinfunction "SLEEP_P$14") (pintype "input"))
    )
    (net (code "29") (name "/SLP4") (class "Default")
      (node (ref "JP18") (pin "7") (pinfunction "7_7") (pintype "passive"))
      (node (ref "R22") (pin "2") (pinfunction "2_2") (pintype "passive"))
      (node (ref "U4") (pin "P$14") (pinfunction "SLEEP_P$14") (pintype "input"))
    )
    (net (code "30") (name "/STP1") (class "Default")
      (node (ref "JP16") (pin "1") (pinfunction "1_1") (pintype "passive"))
      (node (ref "LED1") (pin "A") (pinfunction "A_A") (pintype "passive"))
      (node (ref "U6") (pin "P$16") (pinfunction "STEP_P$16") (pintype "input"))
    )
    (net (code "31") (name "/STP2") (class "Default")
      (node (ref "JP19") (pin "1") (pinfunction "1_1") (pintype "passive"))
      (node (ref "LED4") (pin "A") (pinfunction "A_A") (pintype "passive"))
      (node (ref "U1") (pin "P$16") (pinfunction "STEP_P$16") (pintype "input"))
    )
    (net (code "32") (name "/STP3") (class "Default")
      (node (ref "JP17") (pin "1") (pinfunction "1_1") (pintype "passive"))
      (node (ref "LED2") (pin "A") (pinfunction "A_A") (pintype "passive"))
      (node (ref "U3") (pin "P$16") (pinfunction "STEP_P$16") (pintype "input"))
    )
    (net (code "33") (name "/STP4") (class "Default")
      (node (ref "JP18") (pin "1") (pinfunction "1_1") (pintype "passive"))
      (node (ref "LED3") (pin "A") (pinfunction "A_A") (pintype "passive"))
      (node (ref "U4") (pin "P$16") (pinfunction "STEP_P$16") (pintype "input"))
    )
    (net (code "34") (name "GND") (class "Default")
      (node (ref "C1") (pin "2") (pinfunction "2_2") (pintype "passive"))
      (node (ref "C10") (pin "2") (pinfunction "2_2") (pintype "passive"))
      (node (ref "C11") (pin "2") (pinfunction "2_2") (pintype "passive"))
      (node (ref "C14") (pin "2") (pinfunction "2_2") (pintype "passive"))
      (node (ref "C15") (pin "2") (pinfunction "2_2") (pintype "passive"))
      (node (ref "C16") (pin "2") (pinfunction "2_2") (pintype "passive"))
      (node (ref "C17") (pin "2") (pinfunction "2_2") (pintype "passive"))
      (node (ref "C2") (pin "-") (pinfunction "-_-") (pintype "passive"))
      (node (ref "C20") (pin "2") (pinfunction "2_2") (pintype "passive"))
      (node (ref "C21") (pin "2") (pinfunction "2_2") (pintype "passive"))
      (node (ref "C22") (pin "2") (pinfunction "2_2") (pintype "passive"))
      (node (ref "C23") (pin "2") (pinfunction "2_2") (pintype "passive"))
      (node (ref "C26") (pin "2") (pinfunction "2_2") (pintype "passive"))
      (node (ref "C27") (pin "2") (pinfunction "2_2") (pintype "passive"))
      (node (ref "C28") (pin "2") (pinfunction "2_2") (pintype "passive"))
      (node (ref "C29") (pin "2") (pinfunction "2_2") (pintype "passive"))
      (node (ref "C3") (pin "C") (pinfunction "-_C") (pintype "passive"))
      (node (ref "C4") (pin "2") (pinfunction "2_2") (pintype "passive"))
      (node (ref "C5") (pin "2") (pinfunction "2_2") (pintype "passive"))
      (node (ref "C8") (pin "2") (pinfunction "2_2") (pintype "passive"))
      (node (ref "C9") (pin "2") (pinfunction "2_2") (pintype "passive"))
      (node (ref "JP21") (pin "2") (pinfunction "2_2") (pintype "passive"))
      (node (ref "JP22") (pin "1") (pinfunction "1_1") (pintype "passive"))
      (node (ref "JP22") (pin "2") (pinfunction "2_2") (pintype "passive"))
      (node (ref "JP22") (pin "3") (pinfunction "3_3") (pintype "passive"))
      (node (ref "JP22") (pin "4") (pinfunction "4_4") (pintype "passive"))
      (node (ref "JP27") (pin "1") (pinfunction "1_1") (pintype "passive"))
      (node (ref "JP30") (pin "1") (pinfunction "1_1") (pintype "passive"))
      (node (ref "JP30") (pin "2") (pinfunction "2_2") (pintype "passive"))
      (node (ref "JP30") (pin "3") (pinfunction "3_3") (pintype "passive"))
      (node (ref "JP30") (pin "4") (pinfunction "4_4") (pintype "passive"))
      (node (ref "JP31") (pin "1") (pinfunction "1_1") (pintype "passive"))
      (node (ref "JP31") (pin "2") (pinfunction "2_2") (pintype "passive"))
      (node (ref "JP31") (pin "3") (pinfunction "3_3") (pintype "passive"))
      (node (ref "JP31") (pin "4") (pinfunction "4_4") (pintype "passive"))
      (node (ref "JP32") (pin "1") (pinfunction "1_1") (pintype "passive"))
      (node (ref "JP32") (pin "2") (pinfunction "2_2") (pintype "passive"))
      (node (ref "JP32") (pin "3") (pinfunction "3_3") (pintype "passive"))
      (node (ref "JP32") (pin "4") (pinfunction "4_4") (pintype "passive"))
      (node (ref "JP33") (pin "1") (pinfunction "1_1") (pintype "passive"))
      (node (ref "JP33") (pin "2") (pinfunction "2_2") (pintype "passive"))
      (node (ref "JP33") (pin "3") (pinfunction "3_3") (pintype "passive"))
      (node (ref "R10") (pin "1") (pinfunction "CCW_1") (pintype "passive"))
      (node (ref "R11") (pin "1") (pinfunction "1_1") (pintype "passive"))
      (node (ref "R12") (pin "1") (pinfunction "1_1") (pintype "passive"))
      (node (ref "R13") (pin "2") (pinfunction "2_2") (pintype "passive"))
      (node (ref "R14") (pin "2") (pinfunction "2_2") (pintype "passive"))
      (node (ref "R17") (pin "1") (pinfunction "CCW_1") (pintype "passive"))
      (node (ref "R18") (pin "1") (pinfunction "1_1") (pintype "passive"))
      (node (ref "R19") (pin "1") (pinfunction "1_1") (pintype "passive"))
      (node (ref "R20") (pin "2") (pinfunction "2_2") (pintype "passive"))
      (node (ref "R21") (pin "2") (pinfunction "2_2") (pintype "passive"))
      (node (ref "R24") (pin "1") (pinfunction "CCW_1") (pintype "passive"))
      (node (ref "R25") (pin "1") (pinfunction "1_1") (pintype "passive"))
      (node (ref "R26") (pin "1") (pinfunction "1_1") (pintype "passive"))
      (node (ref "R27") (pin "2") (pinfunction "2_2") (pintype "passive"))
      (node (ref "R28") (pin "2") (pinfunction "2_2") (pintype "passive"))
      (node (ref "R3") (pin "1") (pinfunction "CCW_1") (pintype "passive"))
      (node (ref "R35") (pin "1") (pinfunction "1_1") (pintype "passive"))
      (node (ref "R36") (pin "1") (pinfunction "1_1") (pintype "passive"))
      (node (ref "R4") (pin "1") (pinfunction "1_1") (pintype "passive"))
      (node (ref "R5") (pin "1") (pinfunction "1_1") (pintype "passive"))
      (node (ref "R6") (pin "2") (pinfunction "2_2") (pintype "passive"))
      (node (ref "R7") (pin "2") (pinfunction "2_2") (pintype "passive"))
      (node (ref "SJ1") (pin "2") (pinfunction "2_2") (pintype "passive"))
      (node (ref "U1") (pin "P$18") (pinfunction "GND_P$18") (pintype "power_in"))
      (node (ref "U1") (pin "P$29") (pinfunction "GND_PAD_P$29") (pintype "power_in"))
      (node (ref "U1") (pin "P$3") (pinfunction "GND_P$3") (pintype "power_in"))
      (node (ref "U3") (pin "P$18") (pinfunction "GND_P$18") (pintype "power_in"))
      (node (ref "U3") (pin "P$29") (pinfunction "GND_PAD_P$29") (pintype "power_in"))
      (node (ref "U3") (pin "P$3") (pinfunction "GND_P$3") (pintype "power_in"))
      (node (ref "U4") (pin "P$18") (pinfunction "GND_P$18") (pintype "power_in"))
      (node (ref "U4") (pin "P$29") (pinfunction "GND_PAD_P$29") (pintype "power_in"))
      (node (ref "U4") (pin "P$3") (pinfunction "GND_P$3") (pintype "power_in"))
      (node (ref "U6") (pin "P$18") (pinfunction "GND_P$18") (pintype "power_in"))
      (node (ref "U6") (pin "P$29") (pinfunction "GND_PAD_P$29") (pintype "power_in"))
      (node (ref "U6") (pin "P$3") (pinfunction "GND_P$3") (pintype "power_in"))
    )
    (net (code "35") (name "Net-(LED1-PadC)") (class "Default")
      (node (ref "LED1") (pin "C") (pinfunction "C_C") (pintype "passive"))
      (node (ref "R7") (pin "1") (pinfunction "1_1") (pintype "passive"))
    )
    (net (code "36") (name "Net-(LED2-PadC)") (class "Default")
      (node (ref "LED2") (pin "C") (pinfunction "C_C") (pintype "passive"))
      (node (ref "R14") (pin "1") (pinfunction "1_1") (pintype "passive"))
    )
    (net (code "37") (name "Net-(LED3-PadC)") (class "Default")
      (node (ref "LED3") (pin "C") (pinfunction "C_C") (pintype "passive"))
      (node (ref "R21") (pin "1") (pinfunction "1_1") (pintype "passive"))
    )
    (net (code "38") (name "Net-(LED4-PadC)") (class "Default")
      (node (ref "LED4") (pin "C") (pinfunction "C_C") (pintype "passive"))
      (node (ref "R28") (pin "1") (pinfunction "1_1") (pintype "passive"))
    )
    (net (code "39") (name "Net-(LED5-PadC)") (class "Default")
      (node (ref "LED5") (pin "C") (pinfunction "C_C") (pintype "passive"))
      (node (ref "R36") (pin "2") (pinfunction "2_2") (pintype "passive"))
    )
    (net (code "40") (name "Net-(R2-Pad1)") (class "Default")
      (node (ref "R2") (pin "1") (pinfunction "1_1") (pintype "passive"))
      (node (ref "R35") (pin "2") (pinfunction "2_2") (pintype "passive"))
      (node (ref "SJ1") (pin "1") (pinfunction "1_1") (pintype "passive"))
    )
    (net (code "41") (name "Net-(R3-CW)") (class "Default")
      (node (ref "R3") (pin "3") (pinfunction "CW_3") (pintype "passive"))
      (node (ref "R52") (pin "1") (pinfunction "1_1") (pintype "passive"))
    )
    (net (code "42") (name "Net-(R3-WIPER)") (class "Default")
      (node (ref "R3") (pin "2") (pinfunction "WIPER_2") (pintype "passive"))
      (node (ref "TP1") (pin "P$1") (pinfunction "1_P$1") (pintype "bidirectional"))
      (node (ref "U6") (pin "P$17") (pinfunction "REF_P$17") (pintype "bidirectional"))
    )
    (net (code "43") (name "Net-(R10-CW)") (class "Default")
      (node (ref "R10") (pin "3") (pinfunction "CW_3") (pintype "passive"))
      (node (ref "R49") (pin "1") (pinfunction "1_1") (pintype "passive"))
    )
    (net (code "44") (name "Net-(R10-WIPER)") (class "Default")
      (node (ref "R10") (pin "2") (pinfunction "WIPER_2") (pintype "passive"))
      (node (ref "TP4") (pin "P$1") (pinfunction "1_P$1") (pintype "bidirectional"))
      (node (ref "U3") (pin "P$17") (pinfunction "REF_P$17") (pintype "bidirectional"))
    )
    (net (code "45") (name "Net-(R17-CW)") (class "Default")
      (node (ref "R17") (pin "3") (pinfunction "CW_3") (pintype "passive"))
      (node (ref "R50") (pin "1") (pinfunction "1_1") (pintype "passive"))
    )
    (net (code "46") (name "Net-(R17-WIPER)") (class "Default")
      (node (ref "R17") (pin "2") (pinfunction "WIPER_2") (pintype "passive"))
      (node (ref "TP3") (pin "P$1") (pinfunction "1_P$1") (pintype "bidirectional"))
      (node (ref "U4") (pin "P$17") (pinfunction "REF_P$17") (pintype "bidirectional"))
    )
    (net (code "47") (name "Net-(R24-CW)") (class "Default")
      (node (ref "R24") (pin "3") (pinfunction "CW_3") (pintype "passive"))
      (node (ref "R51") (pin "1") (pinfunction "1_1") (pintype "passive"))
    )
    (net (code "48") (name "Net-(R24-WIPER)") (class "Default")
      (node (ref "R24") (pin "2") (pinfunction "WIPER_2") (pintype "passive"))
      (node (ref "TP2") (pin "P$1") (pinfunction "1_P$1") (pintype "bidirectional"))
      (node (ref "U1") (pin "P$17") (pinfunction "REF_P$17") (pintype "bidirectional"))
    )
    (net (code "49") (name "Net-(U1-CP1)") (class "Default")
      (node (ref "C24") (pin "1") (pinfunction "1_1") (pintype "passive"))
      (node (ref "U1") (pin "P$4") (pinfunction "CP1_P$4") (pintype "bidirectional"))
    )
    (net (code "50") (name "Net-(U1-CP2)") (class "Default")
      (node (ref "C24") (pin "2") (pinfunction "2_2") (pintype "passive"))
      (node (ref "U1") (pin "P$5") (pinfunction "CP2_P$5") (pintype "bidirectional"))
    )
    (net (code "51") (name "Net-(U1-OUT1A)") (class "Default")
      (node (ref "JP14") (pin "2") (pinfunction "2_2") (pintype "passive"))
      (node (ref "JP28") (pin "2") (pinfunction "2_2") (pintype "passive"))
      (node (ref "U1") (pin "P$24") (pinfunction "OUT1A_P$24") (pintype "bidirectional"))
    )
    (net (code "52") (name "Net-(U1-OUT1B)") (class "Default")
      (node (ref "JP14") (pin "1") (pinfunction "1_1") (pintype "passive"))
      (node (ref "JP28") (pin "1") (pinfunction "1_1") (pintype "passive"))
      (node (ref "U1") (pin "P$21") (pinfunction "OUT1B_P$21") (pintype "bidirectional"))
    )
    (net (code "53") (name "Net-(U1-OUT2A)") (class "Default")
      (node (ref "JP15") (pin "1") (pinfunction "1_1") (pintype "passive"))
      (node (ref "JP28") (pin "3") (pinfunction "3_3") (pintype "passive"))
      (node (ref "U1") (pin "P$26") (pinfunction "OUT2A_P$26") (pintype "bidirectional"))
    )
    (net (code "54") (name "Net-(U1-OUT2B)") (class "Default")
      (node (ref "JP15") (pin "2") (pinfunction "2_2") (pintype "passive"))
      (node (ref "JP28") (pin "4") (pinfunction "4_4") (pintype "passive"))
      (node (ref "U1") (pin "P$1") (pinfunction "OUT2B_P$1") (pintype "bidirectional"))
    )
    (net (code "55") (name "Net-(U1-ROSC)") (class "Default")
      (node (ref "R27") (pin "1") (pinfunction "1_1") (pintype "passive"))
      (node (ref "U1") (pin "P$13") (pinfunction "ROSC_P$13") (pintype "bidirectional"))
    )
    (net (code "56") (name "Net-(U1-SENSE1)") (class "Default")
      (node (ref "R25") (pin "2") (pinfunction "2_2") (pintype "passive"))
      (node (ref "U1") (pin "P$23") (pinfunction "SENSE1_P$23") (pintype "bidirectional"))
    )
    (net (code "57") (name "Net-(U1-SENSE2)") (class "Default")
      (node (ref "R26") (pin "2") (pinfunction "2_2") (pintype "passive"))
      (node (ref "U1") (pin "P$27") (pinfunction "SENSE2_P$27") (pintype "bidirectional"))
    )
    (net (code "58") (name "Net-(U1-VCP)") (class "Default")
      (node (ref "C25") (pin "1") (pinfunction "1_1") (pintype "passive"))
      (node (ref "U1") (pin "P$6") (pinfunction "VCP_P$6") (pintype "bidirectional"))
    )
    (net (code "59") (name "Net-(U1-VREG)") (class "Default")
      (node (ref "C26") (pin "1") (pinfunction "1_1") (pintype "passive"))
      (node (ref "U1") (pin "P$8") (pinfunction "VREG_P$8") (pintype "bidirectional"))
    )
    (net (code "60") (name "Net-(U2-GND)") (class "Default")
      (node (ref "R1") (pin "1") (pinfunction "1_1") (pintype "passive"))
      (node (ref "R2") (pin "2") (pinfunction "2_2") (pintype "passive"))
      (node (ref "U2") (pin "1") (pinfunction "GND_1") (pintype "input"))
    )
    (net (code "61") (name "Net-(U2-IN)") (class "Default")
      (node (ref "C5") (pin "1") (pinfunction "1_1") (pintype "passive"))
      (node (ref "F1") (pin "2") (pinfunction "2_2") (pintype "bidirectional"))
      (node (ref "U2") (pin "3") (pinfunction "IN_3") (pintype "input"))
    )
    (net (code "62") (name "Net-(U3-CP1)") (class "Default")
      (node (ref "C12") (pin "1") (pinfunction "1_1") (pintype "passive"))
      (node (ref "U3") (pin "P$4") (pinfunction "CP1_P$4") (pintype "bidirectional"))
    )
    (net (code "63") (name "Net-(U3-CP2)") (class "Default")
      (node (ref "C12") (pin "2") (pinfunction "2_2") (pintype "passive"))
      (node (ref "U3") (pin "P$5") (pinfunction "CP2_P$5") (pintype "bidirectional"))
    )
    (net (code "64") (name "Net-(U3-OUT1A)") (class "Default")
      (node (ref "JP26") (pin "2") (pinfunction "2_2") (pintype "passive"))
      (node (ref "JP5") (pin "2") (pinfunction "2_2") (pintype "passive"))
      (node (ref "U3") (pin "P$24") (pinfunction "OUT1A_P$24") (pintype "bidirectional"))
    )
    (net (code "65") (name "Net-(U3-OUT1B)") (class "Default")
      (node (ref "JP26") (pin "1") (pinfunction "1_1") (pintype "passive"))
      (node (ref "JP5") (pin "1") (pinfunction "1_1") (pintype "passive"))
      (node (ref "U3") (pin "P$21") (pinfunction "OUT1B_P$21") (pintype "bidirectional"))
    )
    (net (code "66") (name "Net-(U3-OUT2A)") (class "Default")
      (node (ref "JP26") (pin "3") (pinfunction "3_3") (pintype "passive"))
      (node (ref "JP6") (pin "1") (pinfunction "1_1") (pintype "passive"))
      (node (ref "U3") (pin "P$26") (pinfunction "OUT2A_P$26") (pintype "bidirectional"))
    )
    (net (code "67") (name "Net-(U3-OUT2B)") (class "Default")
      (node (ref "JP26") (pin "4") (pinfunction "4_4") (pintype "passive"))
      (node (ref "JP6") (pin "2") (pinfunction "2_2") (pintype "passive"))
      (node (ref "U3") (pin "P$1") (pinfunction "OUT2B_P$1") (pintype "bidirectional"))
    )
    (net (code "68") (name "Net-(U3-ROSC)") (class "Default")
      (node (ref "R13") (pin "1") (pinfunction "1_1") (pintype "passive"))
      (node (ref "U3") (pin "P$13") (pinfunction "ROSC_P$13") (pintype "bidirectional"))
    )
    (net (code "69") (name "Net-(U3-SENSE1)") (class "Default")
      (node (ref "R11") (pin "2") (pinfunction "2_2") (pintype "passive"))
      (node (ref "U3") (pin "P$23") (pinfunction "SENSE1_P$23") (pintype "bidirectional"))
    )
    (net (code "70") (name "Net-(U3-SENSE2)") (class "Default")
      (node (ref "R12") (pin "2") (pinfunction "2_2") (pintype "passive"))
      (node (ref "U3") (pin "P$27") (pinfunction "SENSE2_P$27") (pintype "bidirectional"))
    )
    (net (code "71") (name "Net-(U3-VCP)") (class "Default")
      (node (ref "C13") (pin "1") (pinfunction "1_1") (pintype "passive"))
      (node (ref "U3") (pin "P$6") (pinfunction "VCP_P$6") (pintype "bidirectional"))
    )
    (net (code "72") (name "Net-(U3-VREG)") (class "Default")
      (node (ref "C14") (pin "1") (pinfunction "1_1") (pintype "passive"))
      (node (ref "U3") (pin "P$8") (pinfunction "VREG_P$8") (pintype "bidirectional"))
    )
    (net (code "73") (name "Net-(U4-CP1)") (class "Default")
      (node (ref "C18") (pin "1") (pinfunction "1_1") (pintype "passive"))
      (node (ref "U4") (pin "P$4") (pinfunction "CP1_P$4") (pintype "bidirectional"))
    )
    (net (code "74") (name "Net-(U4-CP2)") (class "Default")
      (node (ref "C18") (pin "2") (pinfunction "2_2") (pintype "passive"))
      (node (ref "U4") (pin "P$5") (pinfunction "CP2_P$5") (pintype "bidirectional"))
    )
    (net (code "75") (name "Net-(U4-OUT1A)") (class "Default")
      (node (ref "JP13") (pin "2") (pinfunction "2_2") (pintype "passive"))
      (node (ref "JP7") (pin "2") (pinfunction "2_2") (pintype "passive"))
      (node (ref "U4") (pin "P$24") (pinfunction "OUT1A_P$24") (pintype "bidirectional"))
    )
    (net (code "76") (name "Net-(U4-OUT1B)") (class "Default")
      (node (ref "JP13") (pin "1") (pinfunction "1_1") (pintype "passive"))
      (node (ref "JP7") (pin "1") (pinfunction "1_1") (pintype "passive"))
      (node (ref "U4") (pin "P$21") (pinfunction "OUT1B_P$21") (pintype "bidirectional"))
    )
    (net (code "77") (name "Net-(U4-OUT2A)") (class "Default")
      (node (ref "JP13") (pin "3") (pinfunction "3_3") (pintype "passive"))
      (node (ref "JP8") (pin "1") (pinfunction "1_1") (pintype "passive"))
      (node (ref "U4") (pin "P$26") (pinfunction "OUT2A_P$26") (pintype "bidirectional"))
    )
    (net (code "78") (name "Net-(U4-OUT2B)") (class "Default")
      (node (ref "JP13") (pin "4") (pinfunction "4_4") (pintype "passive"))
      (node (ref "JP8") (pin "2") (pinfunction "2_2") (pintype "passive"))
      (node (ref "U4") (pin "P$1") (pinfunction "OUT2B_P$1") (pintype "bidirectional"))
    )
    (net (code "79") (name "Net-(U4-ROSC)") (class "Default")
      (node (ref "R20") (pin "1") (pinfunction "1_1") (pintype "passive"))
      (node (ref "U4") (pin "P$13") (pinfunction "ROSC_P$13") (pintype "bidirectional"))
    )
    (net (code "80") (name "Net-(U4-SENSE1)") (class "Default")
      (node (ref "R18") (pin "2") (pinfunction "2_2") (pintype "passive"))
      (node (ref "U4") (pin "P$23") (pinfunction "SENSE1_P$23") (pintype "bidirectional"))
    )
    (net (code "81") (name "Net-(U4-SENSE2)") (class "Default")
      (node (ref "R19") (pin "2") (pinfunction "2_2") (pintype "passive"))
      (node (ref "U4") (pin "P$27") (pinfunction "SENSE2_P$27") (pintype "bidirectional"))
    )
    (net (code "82") (name "Net-(U4-VCP)") (class "Default")
      (node (ref "C19") (pin "1") (pinfunction "1_1") (pintype "passive"))
      (node (ref "U4") (pin "P$6") (pinfunction "VCP_P$6") (pintype "bidirectional"))
    )
    (net (code "83") (name "Net-(U4-VREG)") (class "Default")
      (node (ref "C20") (pin "1") (pinfunction "1_1") (pintype "passive"))
      (node (ref "U4") (pin "P$8") (pinfunction "VREG_P$8") (pintype "bidirectional"))
    )
    (net (code "84") (name "Net-(U6-CP1)") (class "Default")
      (node (ref "C6") (pin "1") (pinfunction "1_1") (pintype "passive"))
      (node (ref "U6") (pin "P$4") (pinfunction "CP1_P$4") (pintype "bidirectional"))
    )
    (net (code "85") (name "Net-(U6-CP2)") (class "Default")
      (node (ref "C6") (pin "2") (pinfunction "2_2") (pintype "passive"))
      (node (ref "U6") (pin "P$5") (pinfunction "CP2_P$5") (pintype "bidirectional"))
    )
    (net (code "86") (name "Net-(U6-OUT1A)") (class "Default")
      (node (ref "JP1") (pin "2") (pinfunction "2_2") (pintype "passive"))
      (node (ref "JP29") (pin "2") (pinfunction "2_2") (pintype "passive"))
      (node (ref "U6") (pin "P$24") (pinfunction "OUT1A_P$24") (pintype "bidirectional"))
    )
    (net (code "87") (name "Net-(U6-OUT1B)") (class "Default")
      (node (ref "JP1") (pin "1") (pinfunction "1_1") (pintype "passive"))
      (node (ref "JP29") (pin "1") (pinfunction "1_1") (pintype "passive"))
      (node (ref "U6") (pin "P$21") (pinfunction "OUT1B_P$21") (pintype "bidirectional"))
    )
    (net (code "88") (name "Net-(U6-OUT2A)") (class "Default")
      (node (ref "JP2") (pin "1") (pinfunction "1_1") (pintype "passive"))
      (node (ref "JP29") (pin "3") (pinfunction "3_3") (pintype "passive"))
      (node (ref "U6") (pin "P$26") (pinfunction "OUT2A_P$26") (pintype "bidirectional"))
    )
    (net (code "89") (name "Net-(U6-OUT2B)") (class "Default")
      (node (ref "JP2") (pin "2") (pinfunction "2_2") (pintype "passive"))
      (node (ref "JP29") (pin "4") (pinfunction "4_4") (pintype "passive"))
      (node (ref "U6") (pin "P$1") (pinfunction "OUT2B_P$1") (pintype "bidirectional"))
    )
    (net (code "90") (name "Net-(U6-ROSC)") (class "Default")
      (node (ref "R6") (pin "1") (pinfunction "1_1") (pintype "passive"))
      (node (ref "U6") (pin "P$13") (pinfunction "ROSC_P$13") (pintype "bidirectional"))
    )
    (net (code "91") (name "Net-(U6-SENSE1)") (class "Default")
      (node (ref "R4") (pin "2") (pinfunction "2_2") (pintype "passive"))
      (node (ref "U6") (pin "P$23") (pinfunction "SENSE1_P$23") (pintype "bidirectional"))
    )
    (net (code "92") (name "Net-(U6-SENSE2)") (class "Default")
      (node (ref "R5") (pin "2") (pinfunction "2_2") (pintype "passive"))
      (node (ref "U6") (pin "P$27") (pinfunction "SENSE2_P$27") (pintype "bidirectional"))
    )
    (net (code "93") (name "Net-(U6-VCP)") (class "Default")
      (node (ref "C7") (pin "1") (pinfunction "1_1") (pintype "passive"))
      (node (ref "U6") (pin "P$6") (pinfunction "VCP_P$6") (pintype "bidirectional"))
    )
    (net (code "94") (name "Net-(U6-VREG)") (class "Default")
      (node (ref "C8") (pin "1") (pinfunction "1_1") (pintype "passive"))
      (node (ref "U6") (pin "P$8") (pinfunction "VREG_P$8") (pintype "bidirectional"))
    )
    (net (code "95") (name "VCC") (class "Default")
      (node (ref "C1") (pin "1") (pinfunction "1_1") (pintype "passive"))
      (node (ref "C15") (pin "1") (pinfunction "1_1") (pintype "passive"))
      (node (ref "C21") (pin "1") (pinfunction "1_1") (pintype "passive"))
      (node (ref "C27") (pin "1") (pinfunction "1_1") (pintype "passive"))
      (node (ref "C3") (pin "A") (pinfunction "+_A") (pintype "passive"))
      (node (ref "C4") (pin "1") (pinfunction "1_1") (pintype "passive"))
      (node (ref "C9") (pin "1") (pinfunction "1_1") (pintype "passive"))
      (node (ref "JP34") (pin "1") (pinfunction "1_1") (pintype "passive"))
      (node (ref "JP34") (pin "2") (pinfunction "2_2") (pintype "passive"))
      (node (ref "JP34") (pin "3") (pinfunction "3_3") (pintype "passive"))
      (node (ref "LED5") (pin "A") (pinfunction "A_A") (pintype "passive"))
      (node (ref "R1") (pin "2") (pinfunction "2_2") (pintype "passive"))
      (node (ref "R15") (pin "1") (pinfunction "1_1") (pintype "passive"))
      (node (ref "R16") (pin "1") (pinfunction "1_1") (pintype "passive"))
      (node (ref "R22") (pin "1") (pinfunction "1_1") (pintype "passive"))
      (node (ref "R23") (pin "1") (pinfunction "1_1") (pintype "passive"))
      (node (ref "R29") (pin "1") (pinfunction "1_1") (pintype "passive"))
      (node (ref "R30") (pin "1") (pinfunction "1_1") (pintype "passive"))
      (node (ref "R31") (pin "1") (pinfunction "1_1") (pintype "passive"))
      (node (ref "R32") (pin "1") (pinfunction "1_1") (pintype "passive"))
      (node (ref "R33") (pin "1") (pinfunction "1_1") (pintype "passive"))
      (node (ref "R34") (pin "1") (pinfunction "1_1") (pintype "passive"))
      (node (ref "R37") (pin "1") (pinfunction "1_1") (pintype "passive"))
      (node (ref "R38") (pin "1") (pinfunction "1_1") (pintype "passive"))
      (node (ref "R39") (pin "1") (pinfunction "1_1") (pintype "passive"))
      (node (ref "R40") (pin "1") (pinfunction "1_1") (pintype "passive"))
      (node (ref "R41") (pin "1") (pinfunction "1_1") (pintype "passive"))
      (node (ref "R42") (pin "1") (pinfunction "1_1") (pintype "passive"))
      (node (ref "R43") (pin "1") (pinfunction "1_1") (pintype "passive"))
      (node (ref "R44") (pin "1") (pinfunction "1_1") (pintype "passive"))
      (node (ref "R45") (pin "1") (pinfunction "1_1") (pintype "passive"))
      (node (ref "R46") (pin "1") (pinfunction "1_1") (pintype "passive"))
      (node (ref "R47") (pin "1") (pinfunction "1_1") (pintype "passive"))
      (node (ref "R48") (pin "1") (pinfunction "1_1") (pintype "passive"))
      (node (ref "R49") (pin "2") (pinfunction "2_2") (pintype "passive"))
      (node (ref "R50") (pin "2") (pinfunction "2_2") (pintype "passive"))
      (node (ref "R51") (pin "2") (pinfunction "2_2") (pintype "passive"))
      (node (ref "R52") (pin "2") (pinfunction "2_2") (pintype "passive"))
      (node (ref "R8") (pin "1") (pinfunction "1_1") (pintype "passive"))
      (node (ref "R9") (pin "1") (pinfunction "1_1") (pintype "passive"))
      (node (ref "U1") (pin "P$15") (pinfunction "VDD_P$15") (pintype "power_in"))
      (node (ref "U2") (pin "4") (pinfunction "OUT_4") (pintype "output"))
      (node (ref "U3") (pin "P$15") (pinfunction "VDD_P$15") (pintype "power_in"))
      (node (ref "U4") (pin "P$15") (pinfunction "VDD_P$15") (pintype "power_in"))
      (node (ref "U6") (pin "P$15") (pinfunction "VDD_P$15") (pintype "power_in"))
    )
    (net (code "96") (name "VIN") (class "Default")
      (node (ref "C10") (pin "1") (pinfunction "1_1") (pintype "passive"))
      (node (ref "C11") (pin "1") (pinfunction "1_1") (pintype "passive"))
      (node (ref "C13") (pin "2") (pinfunction "2_2") (pintype "passive"))
      (node (ref "C16") (pin "1") (pinfunction "1_1") (pintype "passive"))
      (node (ref "C17") (pin "1") (pinfunction "1_1") (pintype "passive"))
      (node (ref "C19") (pin "2") (pinfunction "2_2") (pintype "passive"))
      (node (ref "C2") (pin "+") (pinfunction "+_+") (pintype "passive"))
      (node (ref "C22") (pin "1") (pinfunction "1_1") (pintype "passive"))
      (node (ref "C23") (pin "1") (pinfunction "1_1") (pintype "passive"))
      (node (ref "C25") (pin "2") (pinfunction "2_2") (pintype "passive"))
      (node (ref "C28") (pin "1") (pinfunction "1_1") (pintype "passive"))
      (node (ref "C29") (pin "1") (pinfunction "1_1") (pintype "passive"))
      (node (ref "C7") (pin "2") (pinfunction "2_2") (pintype "passive"))
      (node (ref "D1") (pin "C") (pinfunction "C_C") (pintype "passive"))
      (node (ref "F1") (pin "1") (pinfunction "1_1") (pintype "bidirectional"))
      (node (ref "U1") (pin "P$22") (pinfunction "VBB1_P$22") (pintype "bidirectional"))
      (node (ref "U1") (pin "P$28") (pinfunction "VBB2_P$28") (pintype "bidirectional"))
      (node (ref "U3") (pin "P$22") (pinfunction "VBB1_P$22") (pintype "bidirectional"))
      (node (ref "U3") (pin "P$28") (pinfunction "VBB2_P$28") (pintype "bidirectional"))
      (node (ref "U4") (pin "P$22") (pinfunction "VBB1_P$22") (pintype "bidirectional"))
      (node (ref "U4") (pin "P$28") (pinfunction "VBB2_P$28") (pintype "bidirectional"))
      (node (ref "U6") (pin "P$22") (pinfunction "VBB1_P$22") (pintype "bidirectional"))
      (node (ref "U6") (pin "P$28") (pinfunction "VBB2_P$28") (pintype "bidirectional"))
    )
    (net (code "97") (name "unconnected-(U1-NC-PadP$7)") (class "Default")
      (node (ref "U1") (pin "P$7") (pinfunction "NC_P$7") (pintype "no_connect"))
    )
    (net (code "98") (name "unconnected-(U1-NC-PadP$20)") (class "Default")
      (node (ref "U1") (pin "P$20") (pinfunction "NC_P$20") (pintype "no_connect"))
    )
    (net (code "99") (name "unconnected-(U1-NC-PadP$25)") (class "Default")
      (node (ref "U1") (pin "P$25") (pinfunction "NC_P$25") (pintype "no_connect"))
    )
    (net (code "100") (name "unconnected-(U3-NC-PadP$7)") (class "Default")
      (node (ref "U3") (pin "P$7") (pinfunction "NC_P$7") (pintype "no_connect"))
    )
    (net (code "101") (name "unconnected-(U3-NC-PadP$20)") (class "Default")
      (node (ref "U3") (pin "P$20") (pinfunction "NC_P$20") (pintype "no_connect"))
    )
    (net (code "102") (name "unconnected-(U3-NC-PadP$25)") (class "Default")
      (node (ref "U3") (pin "P$25") (pinfunction "NC_P$25") (pintype "no_connect"))
    )
    (net (code "103") (name "unconnected-(U4-NC-PadP$7)") (class "Default")
      (node (ref "U4") (pin "P$7") (pinfunction "NC_P$7") (pintype "no_connect"))
    )
    (net (code "104") (name "unconnected-(U4-NC-PadP$20)") (class "Default")
      (node (ref "U4") (pin "P$20") (pinfunction "NC_P$20") (pintype "no_connect"))
    )
    (net (code "105") (name "unconnected-(U4-NC-PadP$25)") (class "Default")
      (node (ref "U4") (pin "P$25") (pinfunction "NC_P$25") (pintype "no_connect"))
    )
    (net (code "106") (name "unconnected-(U6-NC-PadP$7)") (class "Default")
      (node (ref "U6") (pin "P$7") (pinfunction "NC_P$7") (pintype "no_connect"))
    )
    (net (code "107") (name "unconnected-(U6-NC-PadP$20)") (class "Default")
      (node (ref "U6") (pin "P$20") (pinfunction "NC_P$20") (pintype "no_connect"))
    )
    (net (code "108") (name "unconnected-(U6-NC-PadP$25)") (class "Default")
      (node (ref "U6") (pin "P$25") (pinfunction "NC_P$25") (pintype "no_connect"))
    )
  )
)
